# Buck.net
KiCad netlist of a schematic drawn in Altium Designer
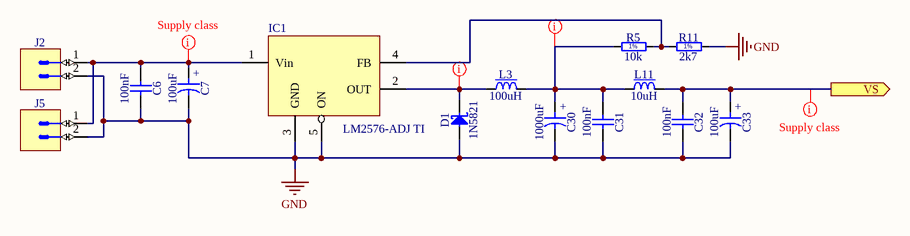
[diagram p0: Buck.SchDoc]

(export (version "E")
  (design (tool "Eeschema 10.0.6"))
  (components
    (comp (ref "C6")
      (value "100nF")
      (footprint "CAPC2012X135N")
      (description "Non-polarised capacitor")
      (fields
        (field (name "PART NUMBER") "CC0805_100NF_50V_10%_X7R")
        (field (name "VOLTAGE") "50V")
        (field (name "AUTHOR") "CERN DEM JLC")
      )
      (libsource (lib "Capacitors") (part "Capacitor - non polarized"))
    )
    (comp (ref "C7")
      (value "100uF")
      (footprint "CAPAE660X540N")
      (description "Polarised capacitor")
      (fields
        (field (name "PART NUMBER") "CAE660-540_100UF_16V_20%")
        (field (name "VOLTAGE") "16V")
        (field (name "AUTHOR") "CERN DEM JLC")
      )
      (libsource (lib "Capacitors") (part "Capacitor - polarized"))
    )
    (comp (ref "C30")
      (value "1000uF")
      (footprint "CAPPR750-1650X1600")
      (description "Polarised capacitor")
      (fields
        (field (name "PART NUMBER") "CAER_1000UF_25V_20%_PANASONIC_EEUFC1E102S")
        (field (name "VOLTAGE") "25V")
        (field (name "AUTHOR") "CERN DEM JMW")
      )
      (libsource (lib "Capacitors") (part "Capacitor - polarized"))
    )
    (comp (ref "C31")
      (value "100nF")
      (footprint "CAPC2012X135N")
      (description "Non-polarised capacitor")
      (fields
        (field (name "PART NUMBER") "CC0805_100NF_50V_10%_X7R")
        (field (name "VOLTAGE") "50V")
        (field (name "AUTHOR") "CERN DEM JLC")
      )
      (libsource (lib "Capacitors") (part "Capacitor - non polarized"))
    )
    (comp (ref "C32")
      (value "100nF")
      (footprint "CAPC2012X135N")
      (description "Non-polarised capacitor")
      (fields
        (field (name "PART NUMBER") "CC0805_100NF_50V_10%_X7R")
        (field (name "VOLTAGE") "50V")
        (field (name "AUTHOR") "CERN DEM JLC")
      )
      (libsource (lib "Capacitors") (part "Capacitor - non polarized"))
    )
    (comp (ref "C33")
      (value "100uF")
      (footprint "CAPAE660X540N")
      (description "Polarised capacitor")
      (fields
        (field (name "PART NUMBER") "CAE660-540_100UF_16V_20%")
        (field (name "VOLTAGE") "16V")
        (field (name "AUTHOR") "CERN DEM JLC")
      )
      (libsource (lib "Capacitors") (part "Capacitor - polarized"))
    )
    (comp (ref "D1")
      (value "1N5821")
      (footprint "DO-201AD")
      (description "Schottky Diode")
      (fields
        (field (name "VOLTAGE") "30V")
        (field (name "POWER") "3A")
        (field (name "AUTHOR") "CERN DEM JLC")
      )
      (libsource (lib "ICs And Semiconductors") (part "Diode Schottky"))
    )
    (comp (ref "IC1")
      (value "LM2576-ADJ TI")
      (footprint "DPAK170P1435X465-6N")
      (fields (field (name "MANUFACTURER") "TI"))
      (libsource (lib "Additional") (part "LM2576-ADJ"))
    )
    (comp (ref "J2")
      (value "~")
      (footprint "CAMDEN_CTB9350/2A")
      (description "Connector 2 Male")
      (fields
        (field (name "PART NUMBER") "CAMDEN_CTB9350/2A")
        (field (name "MANUFACTURER") "CAMDEN")
        (field (name "AUTHOR") "CERN DEM JLC")
      )
      (libsource (lib "Connectors") (part "Connector 2 Male"))
    )
    (comp (ref "J5")
      (value "KK®")
      (footprint "MOLEX_22-04-1021")
      (description "Connector 2 Male")
      (fields
        (field (name "PART NUMBER") "MOLEX_22-04-1021")
        (field (name "MANUFACTURER") "MOLEX")
        (field (name "AUTHOR") "CERN DEM JLC")
      )
      (libsource (lib "Connectors") (part "Connector 2 Male"))
    )
    (comp (ref "L3")
      (value "100uH")
      (footprint "IND_WURTH_WE-PD_XXL")
      (description "Inductor With Core")
      (fields
        (field (name "PART NUMBER") "IND_100UH_20%_WURTH_WE-PD_7447709101")
        (field (name "POWER") "2.5A")
        (field (name "AUTHOR") "CERN DEM JLC")
      )
      (libsource (lib "Inductors & Transformers") (part "Inductor With Magnetic core"))
    )
    (comp (ref "L11")
      (value "10uH")
      (footprint "INDM6965X300N")
      (description "Inductor With Core")
      (fields
        (field (name "PART NUMBER") "IND2525_10UH_20%_VISHAY_IHLP-2525CZ")
        (field (name "POWER") "3A")
        (field (name "AUTHOR") "CERN DEM JLC")
      )
      (libsource (lib "Inductors & Transformers") (part "Inductor With Magnetic core"))
    )
    (comp (ref "R5")
      (value "10k")
      (footprint "RESC2012X60N")
      (description "Resistor - 1%")
      (fields
        (field (name "PART NUMBER") "R0805_10K_1%_0.125W_100PPM")
        (field (name "POWER") "0.125W")
        (field (name "AUTHOR") "CERN DEM JLC")
      )
      (libsource (lib "Resistors") (part "Resistor - 1%"))
    )
    (comp (ref "R11")
      (value "2k7")
      (footprint "RESC2012X60N")
      (description "Resistor - 1%")
      (fields
        (field (name "PART NUMBER") "R0805_2K7_1%_0.125W_100PPM")
        (field (name "POWER") "0.125W")
        (field (name "AUTHOR") "CERN DEM JLC")
      )
      (libsource (lib "Resistors") (part "Resistor - 1%"))
    )
  )
  (nets
    (net (code "1") (name "/VS") (class "Default")
      (node (ref "C32") (pin "1") (pinfunction "1_1") (pintype "passive"))
      (node (ref "C33") (pin "1") (pinfunction "1_1") (pintype "passive"))
      (node (ref "L11") (pin "2") (pinfunction "2_2") (pintype "passive"))
    )
    (net (code "2") (name "GND") (class "Default")
      (node (ref "C30") (pin "2") (pinfunction "2_2") (pintype "passive"))
      (node (ref "C31") (pin "2") (pinfunction "2_2") (pintype "passive"))
      (node (ref "C32") (pin "2") (pinfunction "2_2") (pintype "passive"))
      (node (ref "C33") (pin "2") (pinfunction "2_2") (pintype "passive"))
      (node (ref "C6") (pin "2") (pinfunction "2_2") (pintype "passive"))
      (node (ref "C7") (pin "2") (pinfunction "2_2") (pintype "passive"))
      (node (ref "D1") (pin "2") (pinfunction "A_2") (pintype "passive"))
      (node (ref "IC1") (pin "3") (pinfunction "GND_3") (pintype "passive"))
      (node (ref "IC1") (pin "5") (pinfunction "ON_5") (pintype "passive"))
      (node (ref "J2") (pin "2") (pinfunction "2_2") (pintype "bidirectional"))
      (node (ref "J5") (pin "2") (pinfunction "2_2") (pintype "bidirectional"))
      (node (ref "R11") (pin "2") (pinfunction "2_2") (pintype "passive"))
    )
    (net (code "3") (name "Net-(C30-Pad1)") (class "Default")
      (node (ref "C30") (pin "1") (pinfunction "1_1") (pintype "passive"))
      (node (ref "C31") (pin "1") (pinfunction "1_1") (pintype "passive"))
      (node (ref "L11") (pin "1") (pinfunction "1_1") (pintype "passive"))
      (node (ref "L3") (pin "2") (pinfunction "2_2") (pintype "passive"))
      (node (ref "R5") (pin "1") (pinfunction "1_1") (pintype "passive"))
    )
    (net (code "4") (name "Net-(D1-C)") (class "Default")
      (node (ref "D1") (pin "1") (pinfunction "C_1") (pintype "passive"))
      (node (ref "IC1") (pin "2") (pinfunction "OUT_2") (pintype "passive"))
      (node (ref "L3") (pin "1") (pinfunction "1_1") (pintype "passive"))
    )
    (net (code "5") (name "Net-(IC1-FB)") (class "Default")
      (node (ref "IC1") (pin "4") (pinfunction "FB_4") (pintype "passive"))
      (node (ref "R11") (pin "1") (pinfunction "1_1") (pintype "passive"))
      (node (ref "R5") (pin "2") (pinfunction "2_2") (pintype "passive"))
    )
    (net (code "6") (name "Net-(IC1-Vin)") (class "Default")
      (node (ref "C6") (pin "1") (pinfunction "1_1") (pintype "passive"))
      (node (ref "C7") (pin "1") (pinfunction "1_1") (pintype "passive"))
      (node (ref "IC1") (pin "1") (pinfunction "Vin_1") (pintype "passive"))
      (node (ref "J2") (pin "1") (pinfunction "1_1") (pintype "bidirectional"))
      (node (ref "J5") (pin "1") (pinfunction "1_1") (pintype "bidirectional"))
    )
    (net (code "7") (name "unconnected-(IC1-GND-Pad6)") (class "Default")
      (node (ref "IC1") (pin "6") (pinfunction "GND_6") (pintype "passive"))
    )
  )
)
